# battery.net
KiCad netlist of a schematic drawn in Altium Designer
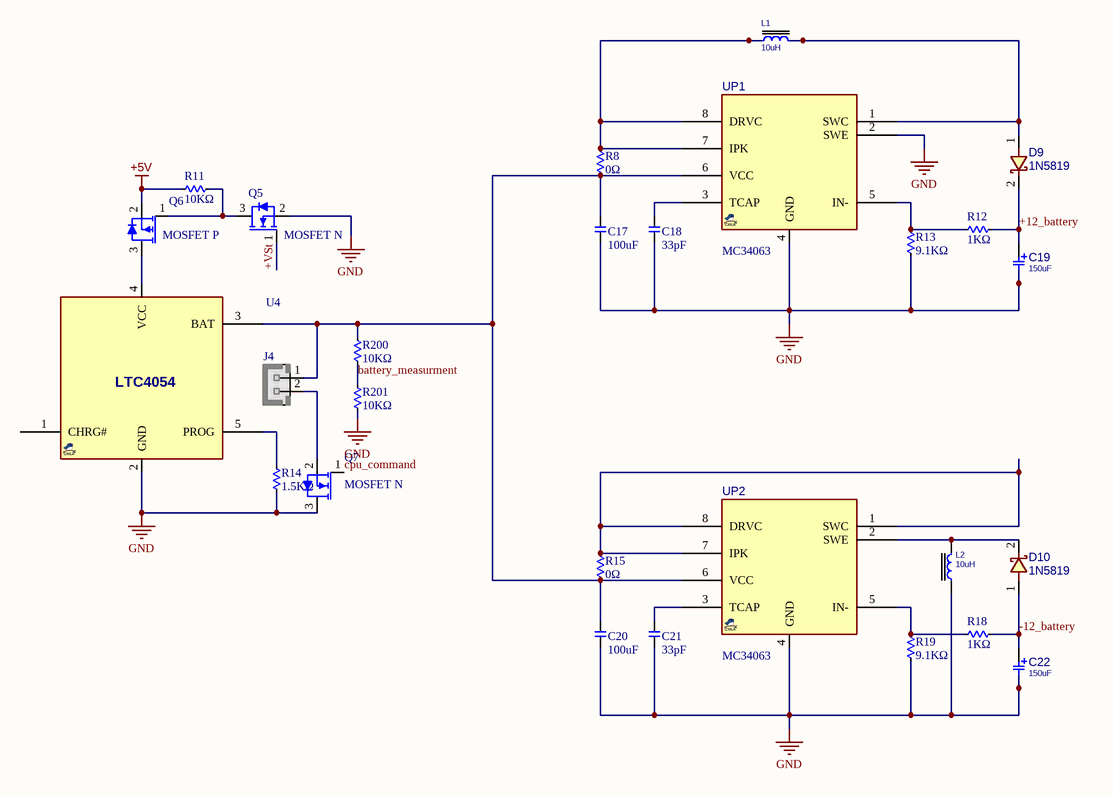
[diagram p0: battery.SchDoc]

(export (version "E")
  (design (tool "Eeschema 10.0.6"))
  (components
    (comp (ref "C17")
      (value "100uF")
      (footprint "CAP 1206 100u")
      (libsource (lib "Shahnahad") (part "CAP 100uF"))
    )
    (comp (ref "C18")
      (value "33pF")
      (footprint "CAP 0603 33p")
      (libsource (lib "Shahnahad") (part "CAP 33pF"))
    )
    (comp (ref "C19")
      (value "150uF")
      (footprint "C_EL_8X12")
      (description "CAP, THD, ELEC,")
      (fields (field (name "MANF_P#") "MANF_PART#") (field (name "MANF") "MANF"))
      (libsource (lib "Chila") (part "CAP_THD_EL"))
    )
    (comp (ref "C20")
      (value "100uF")
      (footprint "CAP 1206 100u")
      (libsource (lib "Shahnahad") (part "CAP 100uF"))
    )
    (comp (ref "C21")
      (value "33pF")
      (footprint "CAP 0603 33p")
      (libsource (lib "Shahnahad") (part "CAP 33pF"))
    )
    (comp (ref "C22")
      (value "150uF")
      (footprint "C_EL_8X12")
      (description "CAP, THD, ELEC,")
      (fields (field (name "MANF_P#") "MANF_PART#") (field (name "MANF") "MANF"))
      (libsource (lib "Chila") (part "CAP_THD_EL"))
    )
    (comp (ref "D9")
      (value "1N5819")
      (footprint "D_SOD123W")
      (description "DIODE, SCHOTTKY, 40V, 1A")
      (fields (field (name "MANF") "DIODES") (field (name "MANF_P#") "1N5819HW-7-F"))
      (libsource (lib "Chila") (part "DIODE_SMD_SCHOTTKY_1N5819"))
    )
    (comp (ref "D10")
      (value "1N5819")
      (footprint "D_SOD123W")
      (description "DIODE, SCHOTTKY, 40V, 1A")
      (fields (field (name "MANF") "DIODES") (field (name "MANF_P#") "1N5819HW-7-F"))
      (libsource (lib "Chila") (part "DIODE_SMD_SCHOTTKY_1N5819"))
    )
    (comp (ref "J4")
      (value "HHDR_2")
      (footprint "XH_2")
      (description "JST-XH pitch: 2.5mm")
      (libsource (lib "Chila") (part "XH_2"))
    )
    (comp (ref "L1")
      (value "10uH")
      (footprint "L_7")
      (description "INDUCTOR, 10uH 2A, 38mOhm, 2626")
      (fields (field (name "MANF_P#") "SRR6038-100Y") (field (name "MANF") "Bourns"))
      (libsource (lib "Chila") (part "IND_SMD_10uH_2A"))
    )
    (comp (ref "L2")
      (value "10uH")
      (footprint "L_7")
      (description "INDUCTOR, 10uH 2A, 38mOhm, 2626")
      (fields (field (name "MANF_P#") "SRR6038-100Y") (field (name "MANF") "Bourns"))
      (libsource (lib "Chila") (part "IND_SMD_10uH_2A"))
    )
    (comp (ref "Q5") (value "MOSFET N") (footprint "SOT23") (libsource (lib "Shahnahad") (part "MOSFET N")))
    (comp (ref "Q6") (value "MOSFET P") (footprint "SOT23") (libsource (lib "Shahnahad") (part "MOSFET P")))
    (comp (ref "Q7") (value "MOSFET N") (footprint "SOT23") (libsource (lib "Shahnahad") (part "MOSFET N")))
    (comp (ref "R8") (value "0Ω") (footprint "RES 0603 0") (libsource (lib "Shahnahad") (part "RES 0")))
    (comp (ref "R11") (value "10KΩ") (footprint "RES 0603 10K") (libsource (lib "") (part "RES 10K_1")))
    (comp (ref "R12") (value "1KΩ") (footprint "RES 0603 1K") (libsource (lib "Shahnahad") (part "RES 1K")))
    (comp (ref "R13") (value "9.1KΩ") (footprint "RES 0603") (libsource (lib "Shahnahad") (part "RES")))
    (comp (ref "R14")
      (value "1.5KΩ")
      (footprint "RES 0603 1.5K")
      (libsource (lib "Shahnahad") (part "RES 1.5K"))
    )
    (comp (ref "R15") (value "0Ω") (footprint "RES 0603 0") (libsource (lib "Shahnahad") (part "RES 0")))
    (comp (ref "R18") (value "1KΩ") (footprint "RES 0603 1K") (libsource (lib "Shahnahad") (part "RES 1K")))
    (comp (ref "R19") (value "9.1KΩ") (footprint "RES 0603") (libsource (lib "Shahnahad") (part "RES")))
    (comp (ref "R200")
      (value "10KΩ")
      (footprint "RES 0603 10K")
      (libsource (lib "Shahnahad") (part "RES 10K"))
    )
    (comp (ref "R201")
      (value "10KΩ")
      (footprint "RES 0603 10K")
      (libsource (lib "Shahnahad") (part "RES 10K"))
    )
    (comp (ref "U4")
      (value "LTC4054")
      (footprint "SOT23_5")
      (description "PWR, CHARGER, Linear, Li-Ion, 0.8A, 4.2v")
      (fields (field (name "MANF") "ANALOG DEVICE/LINEAR") (field (name "MANF_P#") "LTC4054ES5-4.2"))
      (libsource (lib "Chila") (part "LTC4054_SOT23-5"))
    )
    (comp (ref "UP1")
      (value "MC34063")
      (footprint "SO_8")
      (description "REG, Switching, Buck/Boost/Inv, 1.5A, ADJ, 100KHz,3~40VIN, SO-8")
      (fields (field (name "MANF") "TI, ON, HTC") (field (name "MANF_P#") "MC34063AD, HTC34063"))
      (libsource (lib "Chila") (part "VREG_MC34063"))
    )
    (comp (ref "UP2")
      (value "MC34063")
      (footprint "SO_8")
      (description "REG, Switching, Buck/Boost/Inv, 1.5A, ADJ, 100KHz,3~40VIN, SO-8")
      (fields (field (name "MANF") "TI, ON, HTC") (field (name "MANF_P#") "MC34063AD, HTC34063"))
      (libsource (lib "Chila") (part "VREG_MC34063"))
    )
  )
  (nets
    (net (code "1") (name "+5V") (class "Default")
      (node (ref "Q6") (pin "2") (pinfunction "S_2") (pintype "passive"))
      (node (ref "R11") (pin "1") (pintype "passive"))
    )
    (net (code "2") (name "/+12_battery") (class "Default")
      (node (ref "C19") (pin "1") (pinfunction "1_1") (pintype "passive"))
      (node (ref "D9") (pin "2") (pinfunction "2_2") (pintype "passive"))
      (node (ref "R12") (pin "2") (pintype "passive"))
    )
    (net (code "3") (name "/+VSt") (class "Default")
      (node (ref "Q5") (pin "1") (pinfunction "G_1") (pintype "passive"))
    )
    (net (code "4") (name "/-12_battery") (class "Default")
      (node (ref "C22") (pin "1") (pinfunction "1_1") (pintype "passive"))
      (node (ref "D10") (pin "1") (pinfunction "1_1") (pintype "passive"))
      (node (ref "R18") (pin "2") (pintype "passive"))
    )
    (net (code "5") (name "/battery_measurment") (class "Default")
      (node (ref "R200") (pin "2") (pintype "passive"))
      (node (ref "R201") (pin "1") (pintype "passive"))
    )
    (net (code "6") (name "/cpu_command") (class "Default")
      (node (ref "Q7") (pin "1") (pinfunction "G_1") (pintype "passive"))
    )
    (net (code "7") (name "GND") (class "Default")
      (node (ref "C17") (pin "2") (pintype "passive"))
      (node (ref "C18") (pin "2") (pintype "passive"))
      (node (ref "C19") (pin "2") (pinfunction "2_2") (pintype "passive"))
      (node (ref "C20") (pin "2") (pintype "passive"))
      (node (ref "C21") (pin "2") (pintype "passive"))
      (node (ref "C22") (pin "2") (pinfunction "2_2") (pintype "passive"))
      (node (ref "L2") (pin "1") (pinfunction "1_1") (pintype "passive"))
      (node (ref "Q5") (pin "2") (pinfunction "S_2") (pintype "passive"))
      (node (ref "Q7") (pin "3") (pinfunction "D_3") (pintype "passive"))
      (node (ref "R13") (pin "2") (pintype "passive"))
      (node (ref "R14") (pin "1") (pintype "passive"))
      (node (ref "R19") (pin "2") (pintype "passive"))
      (node (ref "R201") (pin "2") (pintype "passive"))
      (node (ref "U4") (pin "2") (pinfunction "GND_2") (pintype "power_in"))
      (node (ref "UP1") (pin "2") (pinfunction "SWE_2") (pintype "passive"))
      (node (ref "UP1") (pin "4") (pinfunction "GND_4") (pintype "power_in"))
      (node (ref "UP2") (pin "4") (pinfunction "GND_4") (pintype "power_in"))
    )
    (net (code "8") (name "Net-(Q5-D)") (class "Default")
      (node (ref "Q5") (pin "3") (pinfunction "D_3") (pintype "passive"))
      (node (ref "Q6") (pin "1") (pinfunction "G_1") (pintype "passive"))
      (node (ref "R11") (pin "2") (pintype "passive"))
    )
    (net (code "9") (name "Net-(Q6-D)") (class "Default")
      (node (ref "Q6") (pin "3") (pinfunction "D_3") (pintype "passive"))
      (node (ref "U4") (pin "4") (pinfunction "VCC_4") (pintype "power_in"))
    )
    (net (code "10") (name "Net-(Q7-S)") (class "Default")
      (node (ref "J4") (pin "2") (pinfunction "2_2") (pintype "passive"))
      (node (ref "Q7") (pin "2") (pinfunction "S_2") (pintype "passive"))
    )
    (net (code "11") (name "Net-(U4-BAT)") (class "Default")
      (node (ref "C17") (pin "1") (pintype "passive"))
      (node (ref "C20") (pin "1") (pintype "passive"))
      (node (ref "J4") (pin "1") (pinfunction "1_1") (pintype "passive"))
      (node (ref "R15") (pin "2") (pintype "passive"))
      (node (ref "R200") (pin "1") (pintype "passive"))
      (node (ref "R8") (pin "2") (pintype "passive"))
      (node (ref "U4") (pin "3") (pinfunction "BAT_3") (pintype "power_in"))
      (node (ref "UP1") (pin "6") (pinfunction "VCC_6") (pintype "power_in"))
      (node (ref "UP2") (pin "6") (pinfunction "VCC_6") (pintype "power_in"))
    )
    (net (code "12") (name "Net-(U4-PROG)") (class "Default")
      (node (ref "R14") (pin "2") (pintype "passive"))
      (node (ref "U4") (pin "5") (pinfunction "PROG_5") (pintype "power_in"))
    )
    (net (code "13") (name "Net-(UP1-DRVC)") (class "Default")
      (node (ref "L1") (pin "1") (pinfunction "1_1") (pintype "passive"))
      (node (ref "R8") (pin "1") (pintype "passive"))
      (node (ref "UP1") (pin "7") (pinfunction "IPK_7") (pintype "passive"))
      (node (ref "UP1") (pin "8") (pinfunction "DRVC_8") (pintype "open_collector"))
    )
    (net (code "14") (name "Net-(UP1-IN-)") (class "Default")
      (node (ref "R12") (pin "1") (pintype "passive"))
      (node (ref "R13") (pin "1") (pintype "passive"))
      (node (ref "UP1") (pin "5") (pinfunction "IN-_5") (pintype "passive"))
    )
    (net (code "15") (name "Net-(UP1-SWC)") (class "Default")
      (node (ref "D9") (pin "1") (pinfunction "1_1") (pintype "passive"))
      (node (ref "L1") (pin "2") (pinfunction "2_2") (pintype "passive"))
      (node (ref "UP1") (pin "1") (pinfunction "SWC_1") (pintype "passive"))
    )
    (net (code "16") (name "Net-(UP1-TCAP)") (class "Default")
      (node (ref "C18") (pin "1") (pintype "passive"))
      (node (ref "UP1") (pin "3") (pinfunction "TCAP_3") (pintype "passive"))
    )
    (net (code "17") (name "Net-(UP2-DRVC)") (class "Default")
      (node (ref "R15") (pin "1") (pintype "passive"))
      (node (ref "UP2") (pin "1") (pinfunction "SWC_1") (pintype "passive"))
      (node (ref "UP2") (pin "7") (pinfunction "IPK_7") (pintype "passive"))
      (node (ref "UP2") (pin "8") (pinfunction "DRVC_8") (pintype "open_collector"))
    )
    (net (code "18") (name "Net-(UP2-IN-)") (class "Default")
      (node (ref "R18") (pin "1") (pintype "passive"))
      (node (ref "R19") (pin "1") (pintype "passive"))
      (node (ref "UP2") (pin "5") (pinfunction "IN-_5") (pintype "passive"))
    )
    (net (code "19") (name "Net-(UP2-SWE)") (class "Default")
      (node (ref "D10") (pin "2") (pinfunction "2_2") (pintype "passive"))
      (node (ref "L2") (pin "2") (pinfunction "2_2") (pintype "passive"))
      (node (ref "UP2") (pin "2") (pinfunction "SWE_2") (pintype "passive"))
    )
    (net (code "20") (name "Net-(UP2-TCAP)") (class "Default")
      (node (ref "C21") (pin "1") (pintype "passive"))
      (node (ref "UP2") (pin "3") (pinfunction "TCAP_3") (pintype "passive"))
    )
    (net (code "21") (name "unconnected-(U4-CHRG#-Pad1)") (class "Default")
      (node (ref "U4") (pin "1") (pinfunction "CHRG#_1") (pintype "power_in"))
    )
  )
)
